# Back.net
KiCad netlist of a schematic drawn in Altium Designer
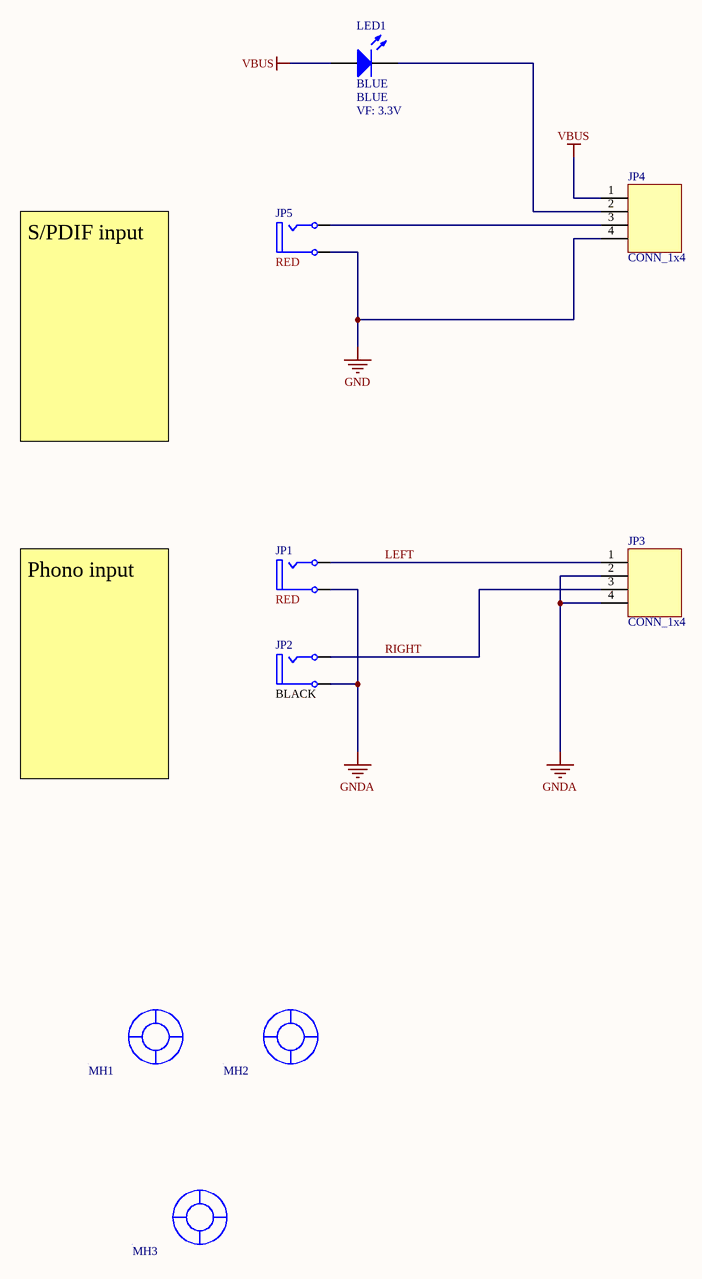
[diagram p0: Back.SchDoc]

(export (version "E")
  (design (tool "Eeschema 10.0.6"))
  (components
    (comp (ref "JP1")
      (value "RED")
      (footprint "CONN_RCA-Lumberg-BTOR")
      (description "RCA panel-mount socket red, 1553 02 rot, Lumberg Connect GmbH")
      (fields (field (name "MPN") "BTOR 1 ROT") (field (name "Comment") "RCA RED"))
      (libsource (lib "micun") (part "CONN_RCA_LUMBERG_BTOR_1_RED"))
    )
    (comp (ref "JP2")
      (value "BLACK")
      (footprint "CONN_RCA-Lumberg-BTOR")
      (description "RCA panel-mount socket red, 1553 02 rot, Lumberg Connect GmbH")
      (fields (field (name "MPN") "BTOR 1 SCHWARZ") (field (name "Comment") "RCA BLACK"))
      (libsource (lib "micun") (part "CONN_RCA_LUMBERG_BTOR_1_BLACK"))
    )
    (comp (ref "JP3")
      (value "CONN_1x4")
      (footprint "CONN_HDR1X4-No3D")
      (description "Header, 4-Pin")
      (fields (field (name "MPN") "0470531000") (field (name "PUBLISHER") "Altium Limited"))
      (libsource (lib "micun") (part "CONN_MHDR_1x4"))
    )
    (comp (ref "JP4")
      (value "CONN_1x4")
      (footprint "CONN_HDR1X4-No3D")
      (description "Header, 4-Pin")
      (fields (field (name "MPN") "0470531000") (field (name "PUBLISHER") "Altium Limited"))
      (libsource (lib "micun") (part "CONN_MHDR_1x4"))
    )
    (comp (ref "JP5")
      (value "RED")
      (footprint "CONN_RCA-Lumberg-BTOR")
      (description "RCA panel-mount socket red, 1553 02 rot, Lumberg Connect GmbH")
      (fields (field (name "MPN") "BTOR 1 ROT") (field (name "Comment") "RCA RED"))
      (libsource (lib "micun") (part "CONN_RCA_LUMBERG_BTOR_1_RED"))
    )
    (comp (ref "LED1")
      (value "BLUE")
      (footprint "LED-KPTL-3216QBC")
      (description "LED BLUE")
      (fields
        (field (name "MPN") "KPTL-3216QBC-D-01")
        (field (name "ALTIUM_VALUE") "BLUE")
        (field (name "VF") "3.3V")
      )
      (libsource (lib "micun") (part "LED-BLUE-KPTL-3216QBC-D-01"))
    )
    (comp (ref "MH1")
      (value "Mounting hole")
      (footprint "MECH_MHOLE_3.5-GND")
      (libsource (lib "micun") (part "MECH_MHOLE"))
    )
    (comp (ref "MH2")
      (value "Mounting hole")
      (footprint "MECH_MHOLE_3.5")
      (libsource (lib "micun") (part "MECH_MHOLE"))
    )
    (comp (ref "MH3")
      (value "Mounting hole")
      (footprint "MECH_USB_MICRO_CUTOUT")
      (libsource (lib "micun") (part "MECH_MICRO_B_CUTOUT"))
    )
  )
  (nets
    (net (code "1") (name "/LEFT") (class "Default")
      (node (ref "JP1") (pin "1") (pinfunction "Signal_1") (pintype "passive"))
      (node (ref "JP3") (pin "1") (pinfunction "1_1") (pintype "passive"))
    )
    (net (code "2") (name "/RIGHT") (class "Default")
      (node (ref "JP2") (pin "1") (pinfunction "Signal_1") (pintype "passive"))
      (node (ref "JP3") (pin "3") (pinfunction "3_3") (pintype "passive"))
    )
    (net (code "3") (name "GND") (class "Default")
      (node (ref "JP4") (pin "4") (pinfunction "4_4") (pintype "passive"))
      (node (ref "JP5") (pin "2") (pinfunction "Ground_2") (pintype "power_in"))
    )
    (net (code "4") (name "GNDA") (class "Default")
      (node (ref "JP1") (pin "2") (pinfunction "Ground_2") (pintype "power_in"))
      (node (ref "JP2") (pin "2") (pinfunction "Ground_2") (pintype "power_in"))
      (node (ref "JP3") (pin "2") (pinfunction "2_2") (pintype "passive"))
      (node (ref "JP3") (pin "4") (pinfunction "4_4") (pintype "passive"))
    )
    (net (code "5") (name "Net-(JP4-Pad2)") (class "Default")
      (node (ref "JP4") (pin "2") (pinfunction "2_2") (pintype "passive"))
      (node (ref "LED1") (pin "K") (pinfunction "K_K") (pintype "passive"))
    )
    (net (code "6") (name "Net-(JP5-Signal)") (class "Default")
      (node (ref "JP4") (pin "3") (pinfunction "3_3") (pintype "passive"))
      (node (ref "JP5") (pin "1") (pinfunction "Signal_1") (pintype "passive"))
    )
    (net (code "7") (name "VBUS") (class "Default")
      (node (ref "JP4") (pin "1") (pinfunction "1_1") (pintype "passive"))
      (node (ref "LED1") (pin "A") (pinfunction "A_A") (pintype "passive"))
    )
  )
)
